# legatus_1_2.net
KiCad netlist of a schematic drawn in EAGLE
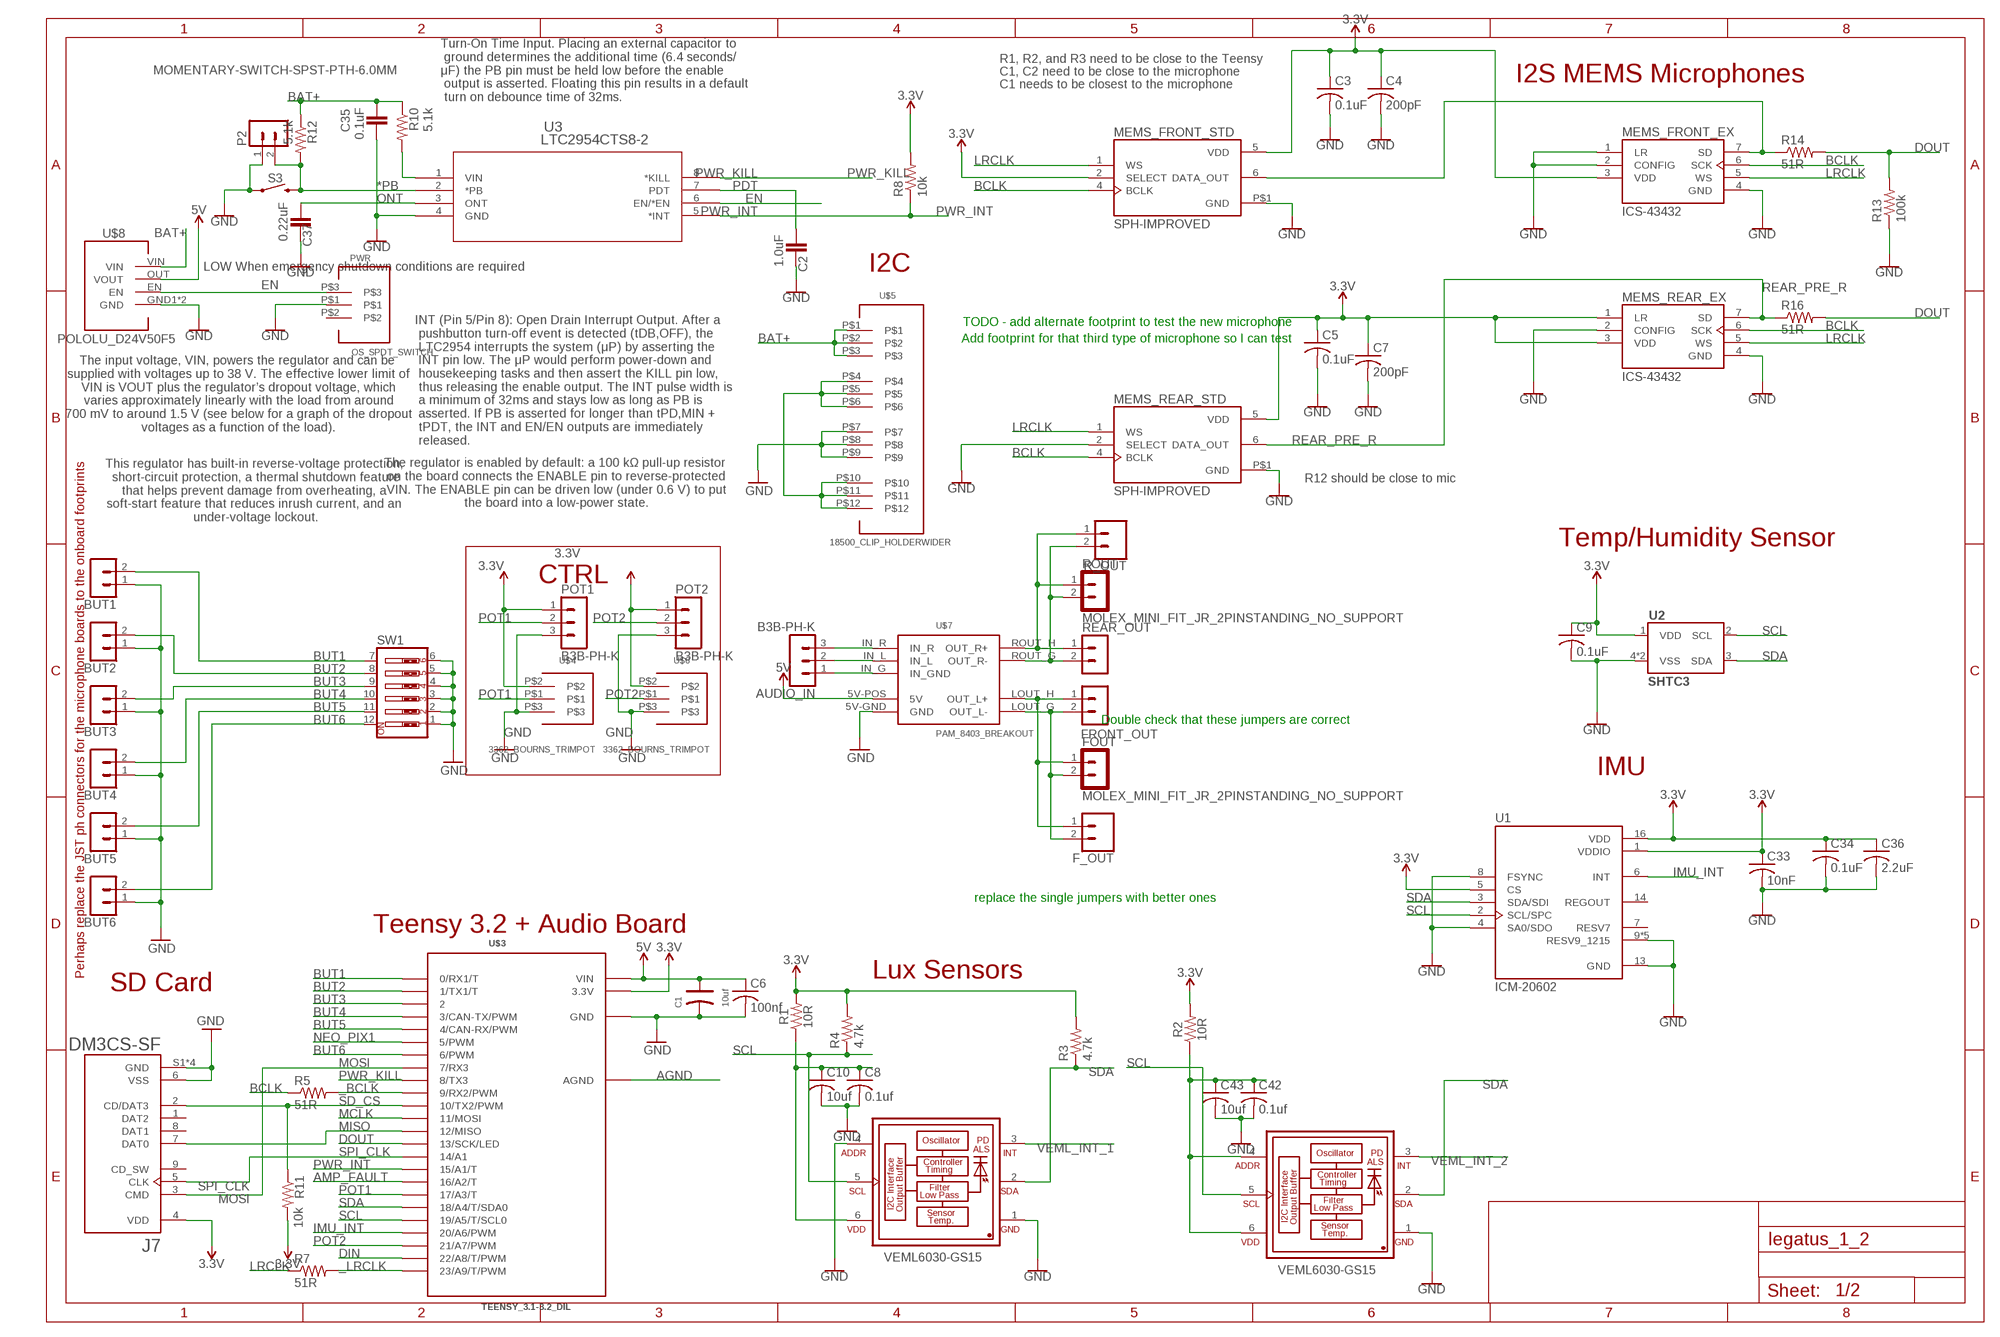
[diagram p0: schematic, sheet 1]
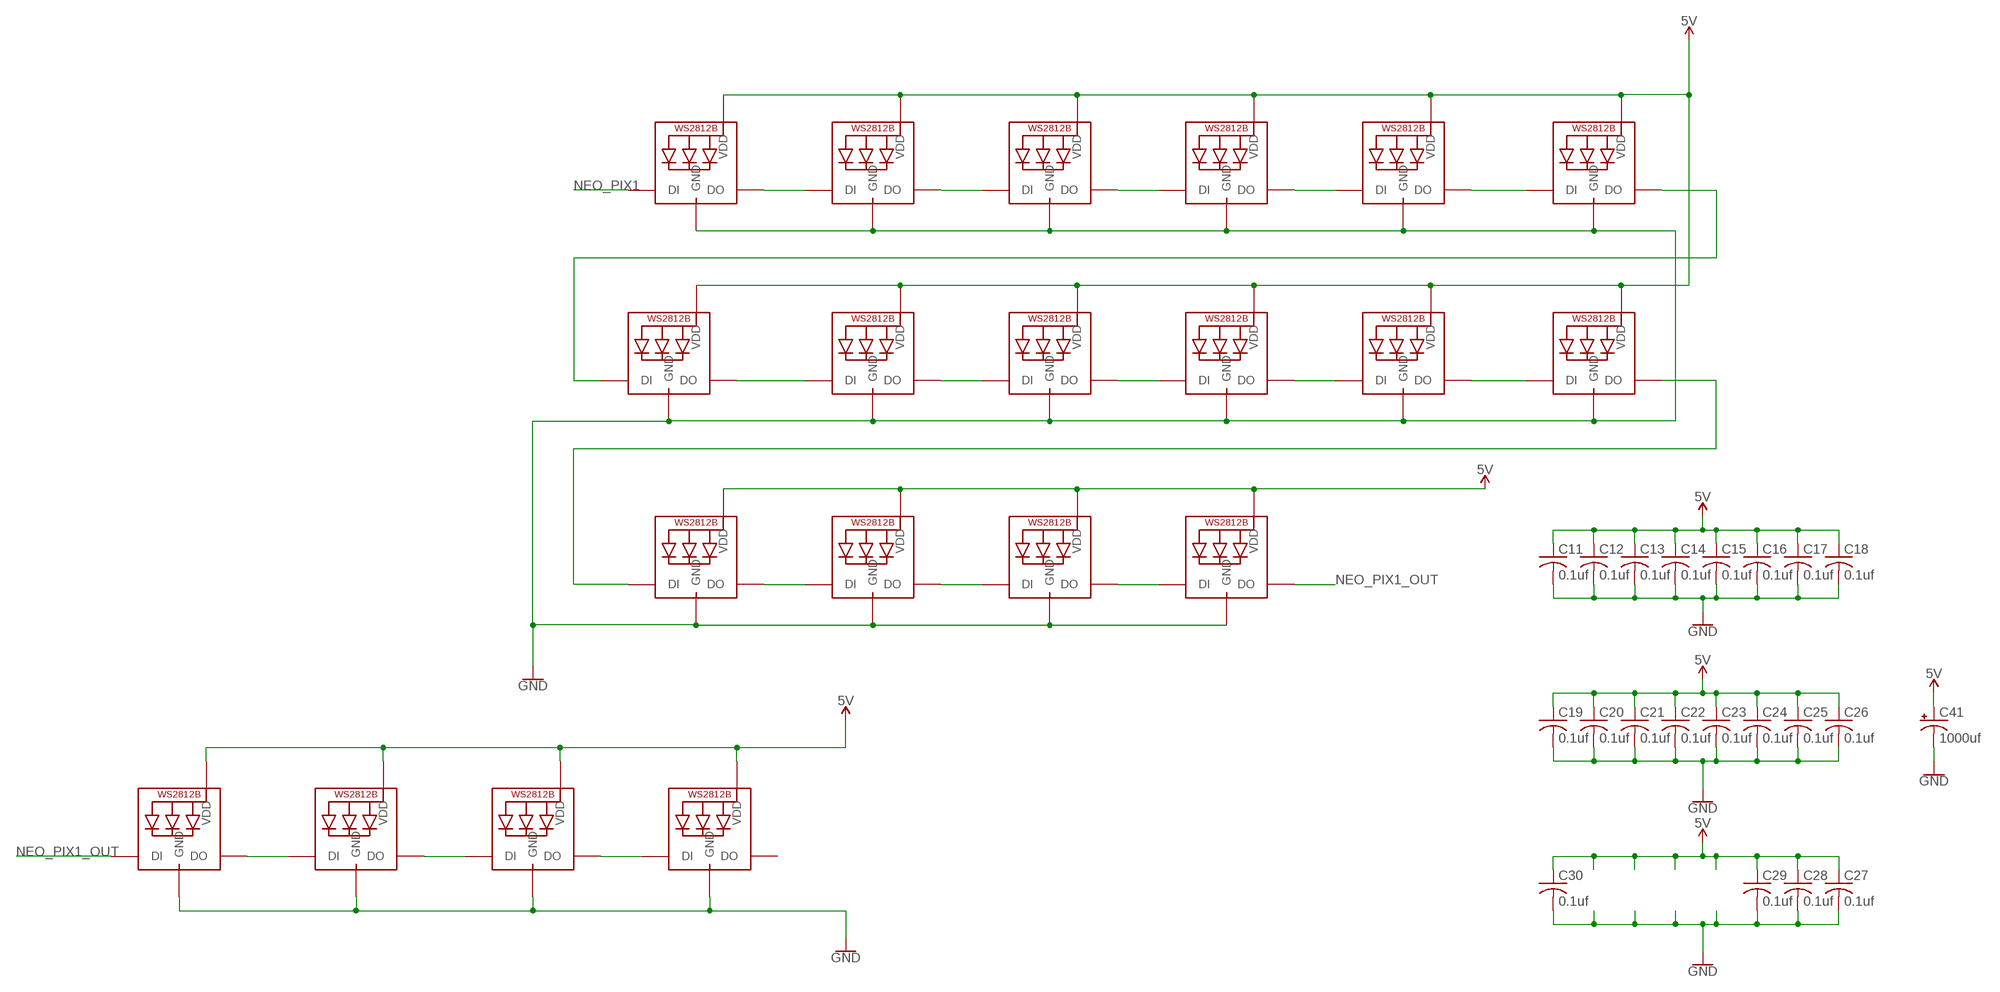
[diagram p1: schematic, sheet 2]

(export (version "E")
  (design (tool "Eeschema 10.0.6"))
  (components
    (comp (ref "C11")
      (value "0.1uf")
      (footprint "eagle-import:C0805")
      (libsource (lib "eagle-import") (part "rcl_334_C-USC0805"))
    )
    (comp (ref "C12")
      (value "0.1uf")
      (footprint "eagle-import:C0805")
      (libsource (lib "eagle-import") (part "rcl_334_C-USC0805"))
    )
    (comp (ref "C13")
      (value "0.1uf")
      (footprint "eagle-import:C0805")
      (libsource (lib "eagle-import") (part "rcl_334_C-USC0805"))
    )
    (comp (ref "C14")
      (value "0.1uf")
      (footprint "eagle-import:C0805")
      (libsource (lib "eagle-import") (part "rcl_334_C-USC0805"))
    )
    (comp (ref "C15")
      (value "0.1uf")
      (footprint "eagle-import:C0805")
      (libsource (lib "eagle-import") (part "rcl_334_C-USC0805"))
    )
    (comp (ref "C16")
      (value "0.1uf")
      (footprint "eagle-import:C0805")
      (libsource (lib "eagle-import") (part "rcl_334_C-USC0805"))
    )
    (comp (ref "C17")
      (value "0.1uf")
      (footprint "eagle-import:C0805")
      (libsource (lib "eagle-import") (part "rcl_334_C-USC0805"))
    )
    (comp (ref "C18")
      (value "0.1uf")
      (footprint "eagle-import:C0805")
      (libsource (lib "eagle-import") (part "rcl_334_C-USC0805"))
    )
    (comp (ref "C19")
      (value "0.1uf")
      (footprint "eagle-import:C0805")
      (libsource (lib "eagle-import") (part "rcl_334_C-USC0805"))
    )
    (comp (ref "C20")
      (value "0.1uf")
      (footprint "eagle-import:C0805")
      (libsource (lib "eagle-import") (part "rcl_334_C-USC0805"))
    )
    (comp (ref "C21")
      (value "0.1uf")
      (footprint "eagle-import:C0805")
      (libsource (lib "eagle-import") (part "rcl_334_C-USC0805"))
    )
    (comp (ref "C22")
      (value "0.1uf")
      (footprint "eagle-import:C0805")
      (libsource (lib "eagle-import") (part "rcl_334_C-USC0805"))
    )
    (comp (ref "C23")
      (value "0.1uf")
      (footprint "eagle-import:C0805")
      (libsource (lib "eagle-import") (part "rcl_334_C-USC0805"))
    )
    (comp (ref "C24")
      (value "0.1uf")
      (footprint "eagle-import:C0805")
      (libsource (lib "eagle-import") (part "rcl_334_C-USC0805"))
    )
    (comp (ref "C25")
      (value "0.1uf")
      (footprint "eagle-import:C0805")
      (libsource (lib "eagle-import") (part "rcl_334_C-USC0805"))
    )
    (comp (ref "C26")
      (value "0.1uf")
      (footprint "eagle-import:C0805")
      (libsource (lib "eagle-import") (part "rcl_334_C-USC0805"))
    )
    (comp (ref "C27")
      (value "0.1uf")
      (footprint "eagle-import:C0805")
      (libsource (lib "eagle-import") (part "rcl_334_C-USC0805"))
    )
    (comp (ref "C28")
      (value "0.1uf")
      (footprint "eagle-import:C0805")
      (libsource (lib "eagle-import") (part "rcl_334_C-USC0805"))
    )
    (comp (ref "C29")
      (value "0.1uf")
      (footprint "eagle-import:C0805")
      (libsource (lib "eagle-import") (part "rcl_334_C-USC0805"))
    )
    (comp (ref "C30")
      (value "0.1uf")
      (footprint "eagle-import:C0805")
      (libsource (lib "eagle-import") (part "rcl_334_C-USC0805"))
    )
    (comp (ref "C41")
      (value "1000uf")
      (footprint "eagle-import:153CLV-1010")
      (libsource (lib "eagle-import") (part "CPOL-US153CLV-1010"))
    )
    (comp (ref "LED1")
      (value "WS2812B_5050N")
      (footprint "eagle-import:WS2812B-NARROW")
      (libsource (lib "eagle-import") (part "WS2812B_5050N"))
    )
    (comp (ref "LED2")
      (value "WS2812B_5050N")
      (footprint "eagle-import:WS2812B-NARROW")
      (libsource (lib "eagle-import") (part "WS2812B_5050N"))
    )
    (comp (ref "LED3")
      (value "WS2812B_5050N")
      (footprint "eagle-import:WS2812B-NARROW")
      (libsource (lib "eagle-import") (part "WS2812B_5050N"))
    )
    (comp (ref "LED4")
      (value "WS2812B_5050N")
      (footprint "eagle-import:WS2812B-NARROW")
      (libsource (lib "eagle-import") (part "WS2812B_5050N"))
    )
    (comp (ref "LED5")
      (value "WS2812B_5050N")
      (footprint "eagle-import:WS2812B-NARROW")
      (libsource (lib "eagle-import") (part "WS2812B_5050N"))
    )
    (comp (ref "LED6")
      (value "WS2812B_5050N")
      (footprint "eagle-import:WS2812B-NARROW")
      (libsource (lib "eagle-import") (part "WS2812B_5050N"))
    )
    (comp (ref "LED7")
      (value "WS2812B_5050N")
      (footprint "eagle-import:WS2812B-NARROW")
      (libsource (lib "eagle-import") (part "WS2812B_5050N"))
    )
    (comp (ref "LED8")
      (value "WS2812B_5050N")
      (footprint "eagle-import:WS2812B-NARROW")
      (libsource (lib "eagle-import") (part "WS2812B_5050N"))
    )
    (comp (ref "LED9")
      (value "WS2812B_5050N")
      (footprint "eagle-import:WS2812B-NARROW")
      (libsource (lib "eagle-import") (part "WS2812B_5050N"))
    )
    (comp (ref "LED10")
      (value "WS2812B_5050N")
      (footprint "eagle-import:WS2812B-NARROW")
      (libsource (lib "eagle-import") (part "WS2812B_5050N"))
    )
    (comp (ref "LED11")
      (value "WS2812B_5050N")
      (footprint "eagle-import:WS2812B-NARROW")
      (libsource (lib "eagle-import") (part "WS2812B_5050N"))
    )
    (comp (ref "LED12")
      (value "WS2812B_5050N")
      (footprint "eagle-import:WS2812B-NARROW")
      (libsource (lib "eagle-import") (part "WS2812B_5050N"))
    )
    (comp (ref "LED13")
      (value "WS2812B_5050N")
      (footprint "eagle-import:WS2812B-NARROW")
      (libsource (lib "eagle-import") (part "WS2812B_5050N"))
    )
    (comp (ref "LED14")
      (value "WS2812B_5050N")
      (footprint "eagle-import:WS2812B-NARROW")
      (libsource (lib "eagle-import") (part "WS2812B_5050N"))
    )
    (comp (ref "LED15")
      (value "WS2812B_5050N")
      (footprint "eagle-import:WS2812B-NARROW")
      (libsource (lib "eagle-import") (part "WS2812B_5050N"))
    )
    (comp (ref "LED16")
      (value "WS2812B_5050N")
      (footprint "eagle-import:WS2812B-NARROW")
      (libsource (lib "eagle-import") (part "WS2812B_5050N"))
    )
    (comp (ref "LED17")
      (value "WS2812B_5050N")
      (footprint "eagle-import:WS2812B-NARROW")
      (libsource (lib "eagle-import") (part "WS2812B_5050N"))
    )
    (comp (ref "LED18")
      (value "WS2812B_5050N")
      (footprint "eagle-import:WS2812B-NARROW")
      (libsource (lib "eagle-import") (part "WS2812B_5050N"))
    )
    (comp (ref "LED19")
      (value "WS2812B_5050N")
      (footprint "eagle-import:WS2812B-NARROW")
      (libsource (lib "eagle-import") (part "WS2812B_5050N"))
    )
    (comp (ref "LED20")
      (value "WS2812B_5050N")
      (footprint "eagle-import:WS2812B-NARROW")
      (libsource (lib "eagle-import") (part "WS2812B_5050N"))
    )
    (comp (ref "AUDIO_IN")
      (value "B3B-PH-K")
      (footprint "eagle-import:B3B-PH-K")
      (libsource (lib "eagle-import") (part "B3B-PH-K"))
    )
    (comp (ref "BUT1")
      (value "B2B-PH-K")
      (footprint "eagle-import:B2B-PH-K")
      (libsource (lib "eagle-import") (part "B2B-PH-K"))
    )
    (comp (ref "BUT2")
      (value "B2B-PH-K")
      (footprint "eagle-import:B2B-PH-K")
      (libsource (lib "eagle-import") (part "B2B-PH-K"))
    )
    (comp (ref "BUT3")
      (value "B2B-PH-K")
      (footprint "eagle-import:B2B-PH-K")
      (libsource (lib "eagle-import") (part "B2B-PH-K"))
    )
    (comp (ref "BUT4")
      (value "B2B-PH-K")
      (footprint "eagle-import:B2B-PH-K")
      (libsource (lib "eagle-import") (part "B2B-PH-K"))
    )
    (comp (ref "BUT5")
      (value "B2B-PH-K")
      (footprint "eagle-import:B2B-PH-K")
      (libsource (lib "eagle-import") (part "B2B-PH-K"))
    )
    (comp (ref "BUT6")
      (value "B2B-PH-K")
      (footprint "eagle-import:B2B-PH-K")
      (libsource (lib "eagle-import") (part "B2B-PH-K"))
    )
    (comp (ref "C1")
      (value "10uf")
      (footprint "eagle-import:PC-D5.3MM")
      (fields (field (name "MPN") "KS 100uF/16V"))
      (libsource (lib "eagle-import") (part "DIP-ALUMINUM-47UF-16V(D5-H7MM)"))
    )
    (comp (ref "C2")
      (value "1.0uF")
      (footprint "eagle-import:CAPC2012X110")
      (libsource (lib "eagle-import") (part "CCHIP-0805(2012-METRIC)_"))
    )
    (comp (ref "C3")
      (value "0.1uF")
      (footprint "eagle-import:C0805")
      (libsource (lib "eagle-import") (part "rcl_334_C-USC0805"))
    )
    (comp (ref "C4")
      (value "200pF")
      (footprint "eagle-import:C0805")
      (libsource (lib "eagle-import") (part "rcl_334_C-USC0805"))
    )
    (comp (ref "C5")
      (value "0.1uF")
      (footprint "eagle-import:C0805")
      (libsource (lib "eagle-import") (part "rcl_334_C-USC0805"))
    )
    (comp (ref "C6")
      (value "100nf")
      (footprint "eagle-import:C2012")
      (libsource (lib "eagle-import") (part "C-USC2012"))
    )
    (comp (ref "C7")
      (value "200pF")
      (footprint "eagle-import:C0805")
      (libsource (lib "eagle-import") (part "rcl_334_C-USC0805"))
    )
    (comp (ref "C8")
      (value "0.1uf")
      (footprint "eagle-import:C0805")
      (libsource (lib "eagle-import") (part "rcl_334_C-USC0805"))
    )
    (comp (ref "C9")
      (value "0.1uF")
      (footprint "eagle-import:C0805")
      (libsource (lib "eagle-import") (part "rcl_334_C-USC0805"))
    )
    (comp (ref "C10")
      (value "10uf")
      (footprint "eagle-import:C0805")
      (libsource (lib "eagle-import") (part "rcl_334_C-USC0805"))
    )
    (comp (ref "C33")
      (value "10nF")
      (footprint "eagle-import:C0805")
      (libsource (lib "eagle-import") (part "rcl_334_C-USC0805"))
    )
    (comp (ref "C34")
      (value "0.1uF")
      (footprint "eagle-import:C0805")
      (libsource (lib "eagle-import") (part "rcl_334_C-USC0805"))
    )
    (comp (ref "C35")
      (value "0.1uF")
      (footprint "eagle-import:CAPC2012X110")
      (libsource (lib "eagle-import") (part "CCHIP-0805(2012-METRIC)_"))
    )
    (comp (ref "C36")
      (value "2.2uF")
      (footprint "eagle-import:C0805")
      (libsource (lib "eagle-import") (part "rcl_334_C-USC0805"))
    )
    (comp (ref "C37")
      (value "0.22uF")
      (footprint "eagle-import:CAPC2012X110")
      (libsource (lib "eagle-import") (part "CCHIP-0805(2012-METRIC)_"))
    )
    (comp (ref "C42")
      (value "0.1uf")
      (footprint "eagle-import:C0805")
      (libsource (lib "eagle-import") (part "rcl_334_C-USC0805"))
    )
    (comp (ref "C43")
      (value "10uf")
      (footprint "eagle-import:C0805")
      (libsource (lib "eagle-import") (part "rcl_334_C-USC0805"))
    )
    (comp (ref "FOUT")
      (value "MOLEX_MINI_FIT_JR_2PINSTANDING_NO_SUPPORT")
      (footprint "eagle-import:MOLEX_MINI_FIT_JR_2_PIN_STANDING_NO_SUPPORTS")
      (libsource (lib "eagle-import") (part "MOLEX_MINI_FIT_JR_2PINSTANDING_NO_SUPPORT"))
    )
    (comp (ref "FRONT_OUT")
      (value "B2B-PH-K")
      (footprint "eagle-import:B2B-PH-K")
      (libsource (lib "eagle-import") (part "B2B-PH-K"))
    )
    (comp (ref "F_OUT")
      (value "CONN_02")
      (footprint "eagle-import:1X02")
      (libsource (lib "eagle-import") (part "CONN_02"))
    )
    (comp (ref "J7")
      (value "DM3CS-SF")
      (footprint "eagle-import:HRS_DM3CS-SF")
      (fields (field (name "MF") "Hirose"))
      (libsource (lib "eagle-import") (part "DM3CS-SF"))
    )
    (comp (ref "MEMS_FRONT_EX")
      (value "ICS-43432")
      (footprint "eagle-import:ICS-43432")
      (fields
        (field (name "DIGIKEY_PARTNO") "1428-1053-2-ND")
        (field (name "MANUFACTURER") "TDK InvenSense")
        (field (name "CREATED_BY") "PCBLayout.com")
      )
      (libsource (lib "eagle-import") (part "ICS-43432"))
    )
    (comp (ref "MEMS_FRONT_STD")
      (value "SPH-IMPROVED")
      (footprint "eagle-import:MIC_SPH0645LM4H-B_LARGER_RING")
      (libsource (lib "eagle-import") (part "SPH-IMPROVED"))
    )
    (comp (ref "MEMS_REAR_EX")
      (value "ICS-43432")
      (footprint "eagle-import:ICS-43432")
      (fields
        (field (name "DIGIKEY_PARTNO") "1428-1053-2-ND")
        (field (name "MANUFACTURER") "TDK InvenSense")
        (field (name "CREATED_BY") "PCBLayout.com")
      )
      (libsource (lib "eagle-import") (part "ICS-43432"))
    )
    (comp (ref "MEMS_REAR_STD")
      (value "SPH-IMPROVED")
      (footprint "eagle-import:MIC_SPH0645LM4H-B_LARGER_RING")
      (libsource (lib "eagle-import") (part "SPH-IMPROVED"))
    )
    (comp (ref "P2")
      (value "B2B-PH-K")
      (footprint "eagle-import:B2B-PH-K")
      (libsource (lib "eagle-import") (part "B2B-PH-K"))
    )
    (comp (ref "POT1")
      (value "B3B-PH-K")
      (footprint "eagle-import:B3B-PH-K")
      (libsource (lib "eagle-import") (part "B3B-PH-K"))
    )
    (comp (ref "POT2")
      (value "B3B-PH-K")
      (footprint "eagle-import:B3B-PH-K")
      (libsource (lib "eagle-import") (part "B3B-PH-K"))
    )
    (comp (ref "PWR")
      (value "OS_SPDT_SWITCH")
      (footprint "eagle-import:OS_SPDT_SLIDE_SWITCH")
      (libsource (lib "eagle-import") (part "OS_SPDT_SWITCH"))
    )
    (comp (ref "R1")
      (value "10R")
      (footprint "eagle-import:R0805")
      (libsource (lib "eagle-import") (part "audio amplifier example_970892_R-US_R0805"))
    )
    (comp (ref "R2")
      (value "10R")
      (footprint "eagle-import:R0805")
      (libsource (lib "eagle-import") (part "audio amplifier example_970892_R-US_R0805"))
    )
    (comp (ref "R3")
      (value "4.7k")
      (footprint "eagle-import:M0805")
      (libsource (lib "eagle-import") (part "adafruit_420_R-US_M0805"))
    )
    (comp (ref "R4")
      (value "4.7k")
      (footprint "eagle-import:M0805")
      (libsource (lib "eagle-import") (part "adafruit_420_R-US_M0805"))
    )
    (comp (ref "R5")
      (value "51R")
      (footprint "eagle-import:M0805")
      (libsource (lib "eagle-import") (part "adafruit_420_R-US_M0805"))
    )
    (comp (ref "R7")
      (value "51R")
      (footprint "eagle-import:M0805")
      (libsource (lib "eagle-import") (part "adafruit_420_R-US_M0805"))
    )
    (comp (ref "R8")
      (value "10k")
      (footprint "eagle-import:R0805")
      (libsource (lib "eagle-import") (part "R-US_R0805"))
    )
    (comp (ref "R10")
      (value "5.1k")
      (footprint "eagle-import:R0805")
      (libsource (lib "eagle-import") (part "R-US_R0805"))
    )
    (comp (ref "R11")
      (value "10k")
      (footprint "eagle-import:M0805")
      (libsource (lib "eagle-import") (part "rcl_R-US_M0805"))
    )
    (comp (ref "R12")
      (value "5.1k")
      (footprint "eagle-import:R0805")
      (libsource (lib "eagle-import") (part "R-US_R0805"))
    )
    (comp (ref "R13")
      (value "100k")
      (footprint "eagle-import:M0805")
      (libsource (lib "eagle-import") (part "adafruit_420_R-US_M0805"))
    )
    (comp (ref "R14")
      (value "51R")
      (footprint "eagle-import:M0805")
      (libsource (lib "eagle-import") (part "adafruit_420_R-US_M0805"))
    )
    (comp (ref "R16")
      (value "51R")
      (footprint "eagle-import:M0805")
      (libsource (lib "eagle-import") (part "adafruit_420_R-US_M0805"))
    )
    (comp (ref "REAR_OUT")
      (value "B2B-PH-K")
      (footprint "eagle-import:B2B-PH-K")
      (libsource (lib "eagle-import") (part "B2B-PH-K"))
    )
    (comp (ref "ROUT")
      (value "MOLEX_MINI_FIT_JR_2PINSTANDING_NO_SUPPORT")
      (footprint "eagle-import:MOLEX_MINI_FIT_JR_2_PIN_STANDING_NO_SUPPORTS")
      (libsource (lib "eagle-import") (part "MOLEX_MINI_FIT_JR_2PINSTANDING_NO_SUPPORT"))
    )
    (comp (ref "R_OUT")
      (value "CONN_02")
      (footprint "eagle-import:1X02")
      (libsource (lib "eagle-import") (part "CONN_02"))
    )
    (comp (ref "S3")
      (value "MOMENTARY-SWITCH-SPST-PTH-6.0MM")
      (footprint "eagle-import:TACTILE_SWITCH_PTH_6.0MM")
      (libsource (lib "eagle-import") (part "MOMENTARY-SWITCH-SPST-PTH-6.0MM"))
    )
    (comp (ref "SW1")
      (value "SW_DIP-6")
      (footprint "eagle-import:EDG-06")
      (libsource (lib "eagle-import") (part "SW_DIP-6"))
    )
    (comp (ref "U$3")
      (value "TEENSY_3.1-3.2_DIL")
      (footprint "eagle-import:TEENSY_3.0-3.2&LC_DIL")
      (libsource (lib "eagle-import") (part "TEENSY_3.1-3.2_DIL"))
    )
    (comp (ref "U$4")
      (value "3362_BOURNS_TRIMPOT")
      (footprint "eagle-import:3362_BOURNS_TRIMPOT")
      (libsource (lib "eagle-import") (part "3362_BOURNS_TRIMPOT"))
    )
    (comp (ref "U$5")
      (value "18500_CLIP_HOLDERWIDER")
      (footprint "eagle-import:3PINBATTERY_CLIP_WIDER")
      (libsource (lib "eagle-import") (part "18500_CLIP_HOLDERWIDER"))
    )
    (comp (ref "U$6")
      (value "3362_BOURNS_TRIMPOT")
      (footprint "eagle-import:3362_BOURNS_TRIMPOT")
      (libsource (lib "eagle-import") (part "3362_BOURNS_TRIMPOT"))
    )
    (comp (ref "U$7")
      (value "PAM_8403_BREAKOUT")
      (footprint "eagle-import:PAM8403_BREAKOUT")
      (libsource (lib "eagle-import") (part "PAM_8403_BREAKOUT"))
    )
    (comp (ref "U$8")
      (value "POLOLU_D24V50F5")
      (footprint "eagle-import:POLOLU_D24V50F5")
      (libsource (lib "eagle-import") (part "POLOLU_D24V50F5"))
    )
    (comp (ref "U1")
      (value "ICM-20602")
      (footprint "eagle-import:PQFN50P300X300X80-16N")
      (fields (field (name "MF") "TDK InvenSense"))
      (libsource (lib "eagle-import") (part "ICM-20602"))
    )
    (comp (ref "U2")
      (value "SHTC3")
      (footprint "eagle-import:SHTC3")
      (libsource (lib "eagle-import") (part "SHTC3"))
    )
    (comp (ref "U3")
      (value "LTC2954CTS8-2")
      (footprint "eagle-import:TSOT-23_TS8")
      (fields (field (name "MF") "Analog Devices / Linear Technology"))
      (libsource (lib "eagle-import") (part "LTC2954CTS8-2"))
    )
    (comp (ref "VMEL_FRONT")
      (value "VEML6030-GS15")
      (footprint "eagle-import:VISHAY_VEML6030_2X2X0.87")
      (fields (field (name "MF") "Vishay Semiconductor"))
      (libsource (lib "eagle-import") (part "VEML6030-GS15"))
    )
    (comp (ref "VMEL_REAR")
      (value "VEML6030-GS15")
      (footprint "eagle-import:VISHAY_VEML6030_2X2X0.87")
      (fields (field (name "MF") "Vishay Semiconductor"))
      (libsource (lib "eagle-import") (part "VEML6030-GS15"))
    )
  )
  (nets
    (net (code "1") (name "*PB") (class "Default")
      (node (ref "P2") (pin "2") (pinfunction "2_2") (pintype "passive"))
      (node (ref "R12") (pin "2") (pinfunction "2_2") (pintype "passive"))
      (node (ref "S3") (pin "3") (pinfunction "2_3") (pintype "passive"))
      (node (ref "U3") (pin "2") (pinfunction "*PB_2") (pintype "input"))
    )
    (net (code "2") (name "3.3V") (class "Default")
      (node (ref "C3") (pin "1") (pinfunction "1_1") (pintype "passive"))
      (node (ref "C33") (pin "1") (pinfunction "1_1") (pintype "passive"))
      (node (ref "C34") (pin "1") (pinfunction "1_1") (pintype "passive"))
      (node (ref "C36") (pin "1") (pinfunction "1_1") (pintype "passive"))
      (node (ref "C4") (pin "1") (pinfunction "1_1") (pintype "passive"))
      (node (ref "C5") (pin "1") (pinfunction "1_1") (pintype "passive"))
      (node (ref "C7") (pin "1") (pinfunction "1_1") (pintype "passive"))
      (node (ref "C9") (pin "1") (pinfunction "1_1") (pintype "passive"))
      (node (ref "J7") (pin "4") (pinfunction "VDD_4") (pintype "passive"))
      (node (ref "MEMS_FRONT_EX") (pin "3") (pinfunction "VDD_3") (pintype "power_in"))
      (node (ref "MEMS_FRONT_STD") (pin "2") (pinfunction "SELECT_2") (pintype "input"))
      (node (ref "MEMS_FRONT_STD") (pin "5") (pinfunction "VDD_5") (pintype "power_in"))
      (node (ref "MEMS_REAR_EX") (pin "1") (pinfunction "LR_1") (pintype "input"))
      (node (ref "MEMS_REAR_EX") (pin "3") (pinfunction "VDD_3") (pintype "power_in"))
      (node (ref "MEMS_REAR_STD") (pin "5") (pinfunction "VDD_5") (pintype "power_in"))
      (node (ref "POT1") (pin "1") (pinfunction "1_1") (pintype "passive"))
      (node (ref "POT2") (pin "1") (pinfunction "1_1") (pintype "passive"))
      (node (ref "R1") (pin "2") (pinfunction "2_2") (pintype "passive"))
      (node (ref "R11") (pin "2") (pinfunction "2_2") (pintype "passive"))
      (node (ref "R2") (pin "2") (pinfunction "2_2") (pintype "passive"))
      (node (ref "R3") (pin "2") (pinfunction "2_2") (pintype "passive"))
      (node (ref "R4") (pin "2") (pinfunction "2_2") (pintype "passive"))
      (node (ref "R8") (pin "2") (pinfunction "2_2") (pintype "passive"))
      (node (ref "U$3") (pin "3.3V") (pinfunction "3.3V_3.3V") (pintype "power_in"))
      (node (ref "U$4") (pin "P$2") (pinfunction "P$2_P$2") (pintype "bidirectional"))
      (node (ref "U$6") (pin "P$2") (pinfunction "P$2_P$2") (pintype "bidirectional"))
      (node (ref "U1") (pin "1") (pinfunction "VDDIO_1") (pintype "power_in"))
      (node (ref "U1") (pin "16") (pinfunction "VDD_16") (pintype "power_in"))
      (node (ref "U1") (pin "5") (pinfunction "CS_5") (pintype "input"))
      (node (ref "U2") (pin "1") (pinfunction "VDD_1") (pintype "bidirectional"))
    )
    (net (code "3") (name "5V") (class "Default")
      (node (ref "C1") (pin "+") (pinfunction "+_+") (pintype "passive"))
      (node (ref "C11") (pin "1") (pinfunction "1_1") (pintype "passive"))
      (node (ref "C12") (pin "1") (pinfunction "1_1") (pintype "passive"))
      (node (ref "C13") (pin "1") (pinfunction "1_1") (pintype "passive"))
      (node (ref "C14") (pin "1") (pinfunction "1_1") (pintype "passive"))
      (node (ref "C15") (pin "1") (pinfunction "1_1") (pintype "passive"))
      (node (ref "C16") (pin "1") (pinfunction "1_1") (pintype "passive"))
      (node (ref "C17") (pin "1") (pinfunction "1_1") (pintype "passive"))
      (node (ref "C18") (pin "1") (pinfunction "1_1") (pintype "passive"))
      (node (ref "C19") (pin "1") (pinfunction "1_1") (pintype "passive"))
      (node (ref "C20") (pin "1") (pinfunction "1_1") (pintype "passive"))
      (node (ref "C21") (pin "1") (pinfunction "1_1") (pintype "passive"))
      (node (ref "C22") (pin "1") (pinfunction "1_1") (pintype "passive"))
      (node (ref "C23") (pin "1") (pinfunction "1_1") (pintype "passive"))
      (node (ref "C24") (pin "1") (pinfunction "1_1") (pintype "passive"))
      (node (ref "C25") (pin "1") (pinfunction "1_1") (pintype "passive"))
      (node (ref "C26") (pin "1") (pinfunction "1_1") (pintype "passive"))
      (node (ref "C27") (pin "1") (pinfunction "1_1") (pintype "passive"))
      (node (ref "C28") (pin "1") (pinfunction "1_1") (pintype "passive"))
      (node (ref "C29") (pin "1") (pinfunction "1_1") (pintype "passive"))
      (node (ref "C30") (pin "1") (pinfunction "1_1") (pintype "passive"))
      (node (ref "C41") (pin "+") (pinfunction "+_+") (pintype "passive"))
      (node (ref "C6") (pin "1") (pinfunction "1_1") (pintype "passive"))
      (node (ref "LED1") (pin "1-VDD") (pinfunction "VDD_1-VDD") (pintype "power_in"))
      (node (ref "LED10") (pin "1-VDD") (pinfunction "VDD_1-VDD") (pintype "power_in"))
      (node (ref "LED11") (pin "1-VDD") (pinfunction "VDD_1-VDD") (pintype "power_in"))
      (node (ref "LED12") (pin "1-VDD") (pinfunction "VDD_1-VDD") (pintype "power_in"))
      (node (ref "LED13") (pin "1-VDD") (pinfunction "VDD_1-VDD") (pintype "power_in"))
      (node (ref "LED14") (pin "1-VDD") (pinfunction "VDD_1-VDD") (pintype "power_in"))
      (node (ref "LED15") (pin "1-VDD") (pinfunction "VDD_1-VDD") (pintype "power_in"))
      (node (ref "LED16") (pin "1-VDD") (pinfunction "VDD_1-VDD") (pintype "power_in"))
      (node (ref "LED17") (pin "1-VDD") (pinfunction "VDD_1-VDD") (pintype "power_in"))
      (node (ref "LED18") (pin "1-VDD") (pinfunction "VDD_1-VDD") (pintype "power_in"))
      (node (ref "LED19") (pin "1-VDD") (pinfunction "VDD_1-VDD") (pintype "power_in"))
      (node (ref "LED2") (pin "1-VDD") (pinfunction "VDD_1-VDD") (pintype "power_in"))
      (node (ref "LED20") (pin "1-VDD") (pinfunction "VDD_1-VDD") (pintype "power_in"))
      (node (ref "LED3") (pin "1-VDD") (pinfunction "VDD_1-VDD") (pintype "power_in"))
      (node (ref "LED4") (pin "1-VDD") (pinfunction "VDD_1-VDD") (pintype "power_in"))
      (node (ref "LED5") (pin "1-VDD") (pinfunction "VDD_1-VDD") (pintype "power_in"))
      (node (ref "LED6") (pin "1-VDD") (pinfunction "VDD_1-VDD") (pintype "power_in"))
      (node (ref "LED7") (pin "1-VDD") (pinfunction "VDD_1-VDD") (pintype "power_in"))
      (node (ref "LED8") (pin "1-VDD") (pinfunction "VDD_1-VDD") (pintype "power_in"))
      (node (ref "LED9") (pin "1-VDD") (pinfunction "VDD_1-VDD") (pintype "power_in"))
      (node (ref "U$3") (pin "VIN") (pinfunction "VIN_VIN") (pintype "power_in"))
      (node (ref "U$7") (pin "5V-POS") (pinfunction "5V_5V-POS") (pintype "bidirectional"))
      (node (ref "U$8") (pin "OUT") (pinfunction "VOUT_OUT") (pintype "bidirectional"))
    )
    (net (code "4") (name "AGND") (class "Default")
      (node (ref "U$3") (pin "AGND") (pinfunction "AGND_AGND") (pintype "power_in"))
    )
    (net (code "5") (name "AMP_FAULT") (class "Default")
      (node (ref "U$3") (pin "16/A2") (pinfunction "16/A2/T_16/A2") (pintype "bidirectional"))
    )
    (net (code "6") (name "BAT+") (class "Default")
      (node (ref "C35") (pin "1") (pinfunction "1_1") (pintype "passive"))
      (node (ref "R10") (pin "1") (pinfunction "1_1") (pintype "passive"))
      (node (ref "R12") (pin "1") (pinfunction "1_1") (pintype "passive"))
      (node (ref "U$5") (pin "P$1") (pinfunction "P$1_P$1") (pintype "bidirectional"))
      (node (ref "U$5") (pin "P$2") (pinfunction "P$2_P$2") (pintype "bidirectional"))
      (node (ref "U$5") (pin "P$3") (pinfunction "P$3_P$3") (pintype "bidirectional"))
      (node (ref "U$8") (pin "VIN") (pinfunction "VIN_VIN") (pintype "bidirectional"))
    )
    (net (code "7") (name "BCLK") (class "Default")
      (node (ref "MEMS_FRONT_EX") (pin "6") (pinfunction "SCK_6") (pintype "input"))
      (node (ref "MEMS_FRONT_STD") (pin "4") (pinfunction "BCLK_4") (pintype "input"))
      (node (ref "MEMS_REAR_EX") (pin "6") (pinfunction "SCK_6") (pintype "input"))
      (node (ref "MEMS_REAR_STD") (pin "4") (pinfunction "BCLK_4") (pintype "input"))
      (node (ref "R5") (pin "1") (pinfunction "1_1") (pintype "passive"))
    )
    (net (code "8") (name "BUT1") (class "Default")
      (node (ref "BUT1") (pin "2") (pinfunction "2_2") (pintype "passive"))
      (node (ref "SW1") (pin "7") (pinfunction "7_7") (pintype "passive"))
      (node (ref "U$3") (pin "0") (pinfunction "0/RX1/T_0") (pintype "bidirectional"))
    )
    (net (code "9") (name "BUT2") (class "Default")
      (node (ref "BUT2") (pin "2") (pinfunction "2_2") (pintype "passive"))
      (node (ref "SW1") (pin "8") (pinfunction "8_8") (pintype "passive"))
      (node (ref "U$3") (pin "1") (pinfunction "1/TX1/T_1") (pintype "bidirectional"))
    )
    (net (code "10") (name "BUT3") (class "Default")
      (node (ref "BUT3") (pin "2") (pinfunction "2_2") (pintype "passive"))
      (node (ref "SW1") (pin "9") (pinfunction "9_9") (pintype "passive"))
      (node (ref "U$3") (pin "2") (pinfunction "2_2") (pintype "bidirectional"))
    )
    (net (code "11") (name "BUT4") (class "Default")
      (node (ref "BUT4") (pin "2") (pinfunction "2_2") (pintype "passive"))
      (node (ref "SW1") (pin "10") (pinfunction "10_10") (pintype "passive"))
      (node (ref "U$3") (pin "3") (pinfunction "3/CAN-TX/PWM_3") (pintype "bidirectional"))
    )
    (net (code "12") (name "BUT5") (class "Default")
      (node (ref "BUT5") (pin "2") (pinfunction "2_2") (pintype "passive"))
      (node (ref "SW1") (pin "11") (pinfunction "11_11") (pintype "passive"))
      (node (ref "U$3") (pin "4") (pinfunction "4/CAN-RX/PWM_4") (pintype "bidirectional"))
    )
    (net (code "13") (name "BUT6") (class "Default")
      (node (ref "BUT6") (pin "2") (pinfunction "2_2") (pintype "passive"))
      (node (ref "SW1") (pin "12") (pinfunction "12_12") (pintype "passive"))
      (node (ref "U$3") (pin "6") (pinfunction "6/PWM_6") (pintype "bidirectional"))
    )
    (net (code "14") (name "DIN") (class "Default")
      (node (ref "U$3") (pin "22/A8") (pinfunction "22/A8/T/PWM_22/A8") (pintype "bidirectional"))
    )
    (net (code "15") (name "DOUT") (class "Default")
      (node (ref "R13") (pin "2") (pinfunction "2_2") (pintype "passive"))
      (node (ref "R14") (pin "2") (pinfunction "2_2") (pintype "passive"))
      (node (ref "R16") (pin "2") (pinfunction "2_2") (pintype "passive"))
      (node (ref "U$3") (pin "13") (pinfunction "13/SCK/LED_13") (pintype "bidirectional"))
    )
    (net (code "16") (name "EN") (class "Default")
      (node (ref "PWR") (pin "P$3") (pinfunction "P$3_P$3") (pintype "bidirectional"))
      (node (ref "U$8") (pin "EN") (pinfunction "EN_EN") (pintype "bidirectional"))
      (node (ref "U3") (pin "6") (pinfunction "EN/*EN_6") (pintype "output"))
    )
    (net (code "17") (name "GND") (class "Default")
      (node (ref "BUT1") (pin "1") (pinfunction "1_1") (pintype "passive"))
      (node (ref "BUT2") (pin "1") (pinfunction "1_1") (pintype "passive"))
      (node (ref "BUT3") (pin "1") (pinfunction "1_1") (pintype "passive"))
      (node (ref "BUT4") (pin "1") (pinfunction "1_1") (pintype "passive"))
      (node (ref "BUT5") (pin "1") (pinfunction "1_1") (pintype "passive"))
      (node (ref "BUT6") (pin "1") (pinfunction "1_1") (pintype "passive"))
      (node (ref "C1") (pin "-") (pinfunction "-_-") (pintype "passive"))
      (node (ref "C10") (pin "2") (pinfunction "2_2") (pintype "passive"))
      (node (ref "C11") (pin "2") (pinfunction "2_2") (pintype "passive"))
      (node (ref "C12") (pin "2") (pinfunction "2_2") (pintype "passive"))
      (node (ref "C13") (pin "2") (pinfunction "2_2") (pintype "passive"))
      (node (ref "C14") (pin "2") (pinfunction "2_2") (pintype "passive"))
      (node (ref "C15") (pin "2") (pinfunction "2_2") (pintype "passive"))
      (node (ref "C16") (pin "2") (pinfunction "2_2") (pintype "passive"))
      (node (ref "C17") (pin "2") (pinfunction "2_2") (pintype "passive"))
      (node (ref "C18") (pin "2") (pinfunction "2_2") (pintype "passive"))
      (node (ref "C19") (pin "2") (pinfunction "2_2") (pintype "passive"))
      (node (ref "C2") (pin "2") (pinfunction "2_2") (pintype "passive"))
      (node (ref "C20") (pin "2") (pinfunction "2_2") (pintype "passive"))
      (node (ref "C21") (pin "2") (pinfunction "2_2") (pintype "passive"))
      (node (ref "C22") (pin "2") (pinfunction "2_2") (pintype "passive"))
      (node (ref "C23") (pin "2") (pinfunction "2_2") (pintype "passive"))
      (node (ref "C24") (pin "2") (pinfunction "2_2") (pintype "passive"))
      (node (ref "C25") (pin "2") (pinfunction "2_2") (pintype "passive"))
      (node (ref "C26") (pin "2") (pinfunction "2_2") (pintype "passive"))
      (node (ref "C27") (pin "2") (pinfunction "2_2") (pintype "passive"))
      (node (ref "C28") (pin "2") (pinfunction "2_2") (pintype "passive"))
      (node (ref "C29") (pin "2") (pinfunction "2_2") (pintype "passive"))
      (node (ref "C3") (pin "2") (pinfunction "2_2") (pintype "passive"))
      (node (ref "C30") (pin "2") (pinfunction "2_2") (pintype "passive"))
      (node (ref "C33") (pin "2") (pinfunction "2_2") (pintype "passive"))
      (node (ref "C34") (pin "2") (pinfunction "2_2") (pintype "passive"))
      (node (ref "C35") (pin "2") (pinfunction "2_2") (pintype "passive"))
      (node (ref "C36") (pin "2") (pinfunction "2_2") (pintype "passive"))
      (node (ref "C37") (pin "2") (pinfunction "2_2") (pintype "passive"))
      (node (ref "C4") (pin "2") (pinfunction "2_2") (pintype "passive"))
      (node (ref "C41") (pin "-") (pinfunction "-_-") (pintype "passive"))
      (node (ref "C42") (pin "2") (pinfunction "2_2") (pintype "passive"))
      (node (ref "C43") (pin "2") (pinfunction "2_2") (pintype "passive"))
      (node (ref "C5") (pin "2") (pinfunction "2_2") (pintype "passive"))
      (node (ref "C6") (pin "2") (pinfunction "2_2") (pintype "passive"))
      (node (ref "C7") (pin "2") (pinfunction "2_2") (pintype "passive"))
      (node (ref "C8") (pin "2") (pinfunction "2_2") (pintype "passive"))
      (node (ref "C9") (pin "2") (pinfunction "2_2") (pintype "passive"))
      (node (ref "J7") (pin "6") (pinfunction "VSS_6") (pintype "passive"))
      (node (ref "J7") (pin "S1") (pinfunction "GND_S1") (pintype "passive"))
      (node (ref "J7") (pin "S2") (pinfunction "GND_S2") (pintype "passive"))
      (node (ref "J7") (pin "S3") (pinfunction "GND_S3") (pintype "passive"))
      (node (ref "J7") (pin "S5") (pinfunction "GND_S5") (pintype "passive"))
      (node (ref "LED1") (pin "3-GND") (pinfunction "GND_3-GND") (pintype "power_in"))
      (node (ref "LED10") (pin "3-GND") (pinfunction "GND_3-GND") (pintype "power_in"))
      (node (ref "LED11") (pin "3-GND") (pinfunction "GND_3-GND") (pintype "power_in"))
      (node (ref "LED12") (pin "3-GND") (pinfunction "GND_3-GND") (pintype "power_in"))
      (node (ref "LED13") (pin "3-GND") (pinfunction "GND_3-GND") (pintype "power_in"))
      (node (ref "LED14") (pin "3-GND") (pinfunction "GND_3-GND") (pintype "power_in"))
      (node (ref "LED15") (pin "3-GND") (pinfunction "GND_3-GND") (pintype "power_in"))
      (node (ref "LED16") (pin "3-GND") (pinfunction "GND_3-GND") (pintype "power_in"))
      (node (ref "LED17") (pin "3-GND") (pinfunction "GND_3-GND") (pintype "power_in"))
      (node (ref "LED18") (pin "3-GND") (pinfunction "GND_3-GND") (pintype "power_in"))
      (node (ref "LED19") (pin "3-GND") (pinfunction "GND_3-GND") (pintype "power_in"))
      (node (ref "LED2") (pin "3-GND") (pinfunction "GND_3-GND") (pintype "power_in"))
      (node (ref "LED20") (pin "3-GND") (pinfunction "GND_3-GND") (pintype "power_in"))
      (node (ref "LED3") (pin "3-GND") (pinfunction "GND_3-GND") (pintype "power_in"))
      (node (ref "LED4") (pin "3-GND") (pinfunction "GND_3-GND") (pintype "power_in"))
      (node (ref "LED5") (pin "3-GND") (pinfunction "GND_3-GND") (pintype "power_in"))
      (node (ref "LED6") (pin "3-GND") (pinfunction "GND_3-GND") (pintype "power_in"))
      (node (ref "LED7") (pin "3-GND") (pinfunction "GND_3-GND") (pintype "power_in"))
      (node (ref "LED8") (pin "3-GND") (pinfunction "GND_3-GND") (pintype "power_in"))
      (node (ref "LED9") (pin "3-GND") (pinfunction "GND_3-GND") (pintype "power_in"))
      (node (ref "MEMS_FRONT_EX") (pin "1") (pinfunction "LR_1") (pintype "input"))
      (node (ref "MEMS_FRONT_EX") (pin "2") (pinfunction "CONFIG_2") (pintype "input"))
      (node (ref "MEMS_FRONT_EX") (pin "4") (pinfunction "GND_4") (pintype "power_in"))
      (node (ref "MEMS_FRONT_STD") (pin "P$1") (pinfunction "GND_P$1") (pintype "power_in"))
      (node (ref "MEMS_REAR_EX") (pin "2") (pinfunction "CONFIG_2") (pintype "input"))
      (node (ref "MEMS_REAR_EX") (pin "4") (pinfunction "GND_4") (pintype "power_in"))
      (node (ref "MEMS_REAR_STD") (pin "2") (pinfunction "SELECT_2") (pintype "input"))
      (node (ref "MEMS_REAR_STD") (pin "P$1") (pinfunction "GND_P$1") (pintype "power_in"))
      (node (ref "P2") (pin "1") (pinfunction "1_1") (pintype "passive"))
      (node (ref "POT1") (pin "3") (pinfunction "3_3") (pintype "passive"))
      (node (ref "POT2") (pin "3") (pinfunction "3_3") (pintype "passive"))
      (node (ref "PWR") (pin "P$1") (pinfunction "P$1_P$1") (pintype "bidirectional"))
      (node (ref "R13") (pin "1") (pinfunction "1_1") (pintype "passive"))
      (node (ref "S3") (pin "1") (pinfunction "1_1") (pintype "passive"))
      (node (ref "SW1") (pin "1") (pinfunction "1_1") (pintype "passive"))
      (node (ref "SW1") (pin "2") (pinfunction "2_2") (pintype "passive"))
      (node (ref "SW1") (pin "3") (pinfunction "3_3") (pintype "passive"))
      (node (ref "SW1") (pin "4") (pinfunction "4_4") (pintype "passive"))
      (node (ref "SW1") (pin "5") (pinfunction "5_5") (pintype "passive"))
      (node (ref "SW1") (pin "6") (pinfunction "6_6") (pintype "passive"))
      (node (ref "U$3") (pin "GND") (pinfunction "GND_GND") (pintype "power_in"))
      (node (ref "U$4") (pin "P$3") (pinfunction "P$3_P$3") (pintype "bidirectional"))
      (node (ref "U$5") (pin "P$7") (pinfunction "P$7_P$7") (pintype "bidirectional"))
      (node (ref "U$5") (pin "P$8") (pinfunction "P$8_P$8") (pintype "bidirectional"))
      (node (ref "U$5") (pin "P$9") (pinfunction "P$9_P$9") (pintype "bidirectional"))
      (node (ref "U$6") (pin "P$3") (pinfunction "P$3_P$3") (pintype "bidirectional"))
      (node (ref "U$7") (pin "5V-GND") (pinfunction "GND_5V-GND") (pintype "bidirectional"))
      (node (ref "U$8") (pin "GND1") (pinfunction "GND_GND1") (pintype "bidirectional"))
      (node (ref "U$8") (pin "GND2") (pinfunction "GND_GND2") (pintype "bidirectional"))
      (node (ref "U1") (pin "10") (pinfunction "RESV9_1215_10") (pintype "passive"))
      (node (ref "U1") (pin "11") (pinfunction "RESV9_1215_11") (pintype "passive"))
      (node (ref "U1") (pin "12") (pinfunction "RESV9_1215_12") (pintype "passive"))
      (node (ref "U1") (pin "13") (pinfunction "GND_13") (pintype "power_in"))
      (node (ref "U1") (pin "15") (pinfunction "RESV9_1215_15") (pintype "passive"))
      (node (ref "U1") (pin "4") (pinfunction "SA0/SDO_4") (pintype "output"))
      (node (ref "U1") (pin "8") (pinfunction "FSYNC_8") (pintype "input"))
      (node (ref "U1") (pin "9") (pinfunction "RESV9_1215_9") (pintype "passive"))
      (node (ref "U2") (pin "4") (pinfunction "VSS_4") (pintype "bidirectional"))
      (node (ref "U2") (pin "5") (pinfunction "VSS_5") (pintype "bidirectional"))
      (node (ref "U3") (pin "4") (pinfunction "GND_4") (pintype "power_in"))
      (node (ref "VMEL_FRONT") (pin "1") (pinfunction "GND_1") (pintype "power_in"))
      (node (ref "VMEL_FRONT") (pin "4") (pinfunction "ADDR_4") (pintype "bidirectional"))
      (node (ref "VMEL_REAR") (pin "1") (pinfunction "GND_1") (pintype "power_in"))
    )
    (net (code "18") (name "IMU_INT") (class "Default")
      (node (ref "U$3") (pin "20/A6") (pinfunction "20/A6/PWM_20/A6") (pintype "bidirectional"))
      (node (ref "U1") (pin "6") (pinfunction "INT_6") (pintype "output"))
    )
    (net (code "19") (name "LRCLK") (class "Default")
      (node (ref "MEMS_FRONT_EX") (pin "5") (pinfunction "WS_5") (pintype "input"))
      (node (ref "MEMS_FRONT_STD") (pin "1") (pinfunction "WS_1") (pintype "input"))
      (node (ref "MEMS_REAR_EX") (pin "5") (pinfunction "WS_5") (pintype "input"))
      (node (ref "MEMS_REAR_STD") (pin "1") (pinfunction "WS_1") (pintype "input"))
      (node (ref "R7") (pin "1") (pinfunction "1_1") (pintype "passive"))
    )
    (net (code "20") (name "MCLK") (class "Default")
      (node (ref "U$3") (pin "11") (pinfunction "11/MOSI_11") (pintype "bidirectional"))
    )
    (net (code "21") (name "MISO") (class "Default")
      (node (ref "J7") (pin "7") (pinfunction "DAT0_7") (pintype "passive"))
      (node (ref "U$3") (pin "12") (pinfunction "12/MISO_12") (pintype "bidirectional"))
    )
    (net (code "22") (name "MOSI") (class "Default")
      (node (ref "J7") (pin "3") (pinfunction "CMD_3") (pintype "passive"))
      (node (ref "U$3") (pin "7") (pinfunction "7/RX3_7") (pintype "bidirectional"))
    )
    (net (code "23") (name "NEO_PIX1") (class "Default")
      (node (ref "LED1") (pin "4-DIN") (pinfunction "DI_4-DIN") (pintype "input"))
      (node (ref "U$3") (pin "5") (pinfunction "5/PWM_5") (pintype "bidirectional"))
    )
    (net (code "24") (name "NEO_PIX1_OUT") (class "Default")
      (node (ref "LED16") (pin "2-DOUT") (pinfunction "DO_2-DOUT") (pintype "output"))
      (node (ref "LED17") (pin "4-DIN") (pinfunction "DI_4-DIN") (pintype "input"))
    )
    (net (code "25") (name "Net-(AUDIO_IN-Pad2)") (class "Default")
      (node (ref "AUDIO_IN") (pin "2") (pinfunction "2_2") (pintype "passive"))
      (node (ref "U$7") (pin "IN_L") (pinfunction "IN_L_IN_L") (pintype "bidirectional"))
    )
    (net (code "26") (name "Net-(AUDIO_IN-Pad3)") (class "Default")
      (node (ref "AUDIO_IN") (pin "3") (pinfunction "3_3") (pintype "passive"))
      (node (ref "U$7") (pin "IN_R") (pinfunction "IN_R_IN_R") (pintype "bidirectional"))
    )
    (net (code "27") (name "Net-(LED1-DO)") (class "Default")
      (node (ref "LED1") (pin "2-DOUT") (pinfunction "DO_2-DOUT") (pintype "output"))
      (node (ref "LED2") (pin "4-DIN") (pinfunction "DI_4-DIN") (pintype "input"))
    )
    (net (code "28") (name "Net-(LED2-DO)") (class "Default")
      (node (ref "LED2") (pin "2-DOUT") (pinfunction "DO_2-DOUT") (pintype "output"))
      (node (ref "LED3") (pin "4-DIN") (pinfunction "DI_4-DIN") (pintype "input"))
    )
    (net (code "29") (name "Net-(LED3-DO)") (class "Default")
      (node (ref "LED3") (pin "2-DOUT") (pinfunction "DO_2-DOUT") (pintype "output"))
      (node (ref "LED4") (pin "4-DIN") (pinfunction "DI_4-DIN") (pintype "input"))
    )
    (net (code "30") (name "Net-(LED4-DO)") (class "Default")
      (node (ref "LED4") (pin "2-DOUT") (pinfunction "DO_2-DOUT") (pintype "output"))
      (node (ref "LED5") (pin "4-DIN") (pinfunction "DI_4-DIN") (pintype "input"))
    )
    (net (code "31") (name "Net-(LED5-DO)") (class "Default")
      (node (ref "LED5") (pin "2-DOUT") (pinfunction "DO_2-DOUT") (pintype "output"))
      (node (ref "LED6") (pin "4-DIN") (pinfunction "DI_4-DIN") (pintype "input"))
    )
    (net (code "32") (name "Net-(LED6-DO)") (class "Default")
      (node (ref "LED6") (pin "2-DOUT") (pinfunction "DO_2-DOUT") (pintype "output"))
      (node (ref "LED7") (pin "4-DIN") (pinfunction "DI_4-DIN") (pintype "input"))
    )
    (net (code "33") (name "Net-(LED7-DO)") (class "Default")
      (node (ref "LED7") (pin "2-DOUT") (pinfunction "DO_2-DOUT") (pintype "output"))
      (node (ref "LED8") (pin "4-DIN") (pinfunction "DI_4-DIN") (pintype "input"))
    )
    (net (code "34") (name "Net-(LED8-DO)") (class "Default")
      (node (ref "LED8") (pin "2-DOUT") (pinfunction "DO_2-DOUT") (pintype "output"))
      (node (ref "LED9") (pin "4-DIN") (pinfunction "DI_4-DIN") (pintype "input"))
    )
    (net (code "35") (name "Net-(LED10-DI)") (class "Default")
      (node (ref "LED10") (pin "4-DIN") (pinfunction "DI_4-DIN") (pintype "input"))
      (node (ref "LED9") (pin "2-DOUT") (pinfunction "DO_2-DOUT") (pintype "output"))
    )
    (net (code "36") (name "Net-(LED10-DO)") (class "Default")
      (node (ref "LED10") (pin "2-DOUT") (pinfunction "DO_2-DOUT") (pintype "output"))
      (node (ref "LED11") (pin "4-DIN") (pinfunction "DI_4-DIN") (pintype "input"))
    )
    (net (code "37") (name "Net-(LED11-DO)") (class "Default")
      (node (ref "LED11") (pin "2-DOUT") (pinfunction "DO_2-DOUT") (pintype "output"))
      (node (ref "LED12") (pin "4-DIN") (pinfunction "DI_4-DIN") (pintype "input"))
    )
    (net (code "38") (name "Net-(LED12-DO)") (class "Default")
      (node (ref "LED12") (pin "2-DOUT") (pinfunction "DO_2-DOUT") (pintype "output"))
      (node (ref "LED13") (pin "4-DIN") (pinfunction "DI_4-DIN") (pintype "input"))
    )
    (net (code "39") (name "Net-(LED13-DO)") (class "Default")
      (node (ref "LED13") (pin "2-DOUT") (pinfunction "DO_2-DOUT") (pintype "output"))
      (node (ref "LED14") (pin "4-DIN") (pinfunction "DI_4-DIN") (pintype "input"))
    )
    (net (code "40") (name "Net-(LED14-DO)") (class "Default")
      (node (ref "LED14") (pin "2-DOUT") (pinfunction "DO_2-DOUT") (pintype "output"))
      (node (ref "LED15") (pin "4-DIN") (pinfunction "DI_4-DIN") (pintype "input"))
    )
    (net (code "41") (name "Net-(LED15-DO)") (class "Default")
      (node (ref "LED15") (pin "2-DOUT") (pinfunction "DO_2-DOUT") (pintype "output"))
      (node (ref "LED16") (pin "4-DIN") (pinfunction "DI_4-DIN") (pintype "input"))
    )
    (net (code "42") (name "Net-(LED17-DO)") (class "Default")
      (node (ref "LED17") (pin "2-DOUT") (pinfunction "DO_2-DOUT") (pintype "output"))
      (node (ref "LED18") (pin "4-DIN") (pinfunction "DI_4-DIN") (pintype "input"))
    )
    (net (code "43") (name "Net-(LED18-DO)") (class "Default")
      (node (ref "LED18") (pin "2-DOUT") (pinfunction "DO_2-DOUT") (pintype "output"))
      (node (ref "LED19") (pin "4-DIN") (pinfunction "DI_4-DIN") (pintype "input"))
    )
    (net (code "44") (name "Net-(LED19-DO)") (class "Default")
      (node (ref "LED19") (pin "2-DOUT") (pinfunction "DO_2-DOUT") (pintype "output"))
      (node (ref "LED20") (pin "4-DIN") (pinfunction "DI_4-DIN") (pintype "input"))
    )
    (net (code "45") (name "Net-(MEMS_FRONT_EX-SD)") (class "Default")
      (node (ref "MEMS_FRONT_EX") (pin "7") (pinfunction "SD_7") (pintype "output"))
      (node (ref "MEMS_FRONT_STD") (pin "6") (pinfunction "DATA_OUT_6") (pintype "output"))
      (node (ref "R14") (pin "1") (pinfunction "1_1") (pintype "passive"))
    )
    (net (code "46") (name "Net-(U$5-PadP$10)") (class "Default")
      (node (ref "U$5") (pin "P$10") (pinfunction "P$10_P$10") (pintype "bidirectional"))
      (node (ref "U$5") (pin "P$11") (pinfunction "P$11_P$11") (pintype "bidirectional"))
      (node (ref "U$5") (pin "P$12") (pinfunction "P$12_P$12") (pintype "bidirectional"))
      (node (ref "U$5") (pin "P$4") (pinfunction "P$4_P$4") (pintype "bidirectional"))
      (node (ref "U$5") (pin "P$5") (pinfunction "P$5_P$5") (pintype "bidirectional"))
      (node (ref "U$5") (pin "P$6") (pinfunction "P$6_P$6") (pintype "bidirectional"))
    )
    (net (code "47") (name "Net-(U$7-IN_GND)") (class "Default")
      (node (ref "AUDIO_IN") (pin "1") (pinfunction "1_1") (pintype "passive"))
      (node (ref "U$7") (pin "IN_G") (pinfunction "IN_GND_IN_G") (pintype "bidirectional"))
    )
    (net (code "48") (name "Net-(U$7-OUT_L+)") (class "Default")
      (node (ref "FOUT") (pin "1") (pinfunction "1_1") (pintype "passive"))
      (node (ref "FRONT_OUT") (pin "1") (pinfunction "1_1") (pintype "passive"))
      (node (ref "F_OUT") (pin "1") (pinfunction "1_1") (pintype "passive"))
      (node (ref "U$7") (pin "LOUT_H") (pinfunction "OUT_L+_LOUT_H") (pintype "bidirectional"))
    )
    (net (code "49") (name "Net-(U$7-OUT_L-)") (class "Default")
      (node (ref "FOUT") (pin "2") (pinfunction "2_2") (pintype "passive"))
      (node (ref "FRONT_OUT") (pin "2") (pinfunction "2_2") (pintype "passive"))
      (node (ref "F_OUT") (pin "2") (pinfunction "2_2") (pintype "passive"))
      (node (ref "U$7") (pin "LOUT_G") (pinfunction "OUT_L-_LOUT_G") (pintype "bidirectional"))
    )
    (net (code "50") (name "Net-(U$7-OUT_R+)") (class "Default")
      (node (ref "REAR_OUT") (pin "1") (pinfunction "1_1") (pintype "passive"))
      (node (ref "ROUT") (pin "1") (pinfunction "1_1") (pintype "passive"))
      (node (ref "R_OUT") (pin "1") (pinfunction "1_1") (pintype "passive"))
      (node (ref "U$7") (pin "ROUT_H") (pinfunction "OUT_R+_ROUT_H") (pintype "bidirectional"))
    )
    (net (code "51") (name "Net-(U$7-OUT_R-)") (class "Default")
      (node (ref "REAR_OUT") (pin "2") (pinfunction "2_2") (pintype "passive"))
      (node (ref "ROUT") (pin "2") (pinfunction "2_2") (pintype "passive"))
      (node (ref "R_OUT") (pin "2") (pinfunction "2_2") (pintype "passive"))
      (node (ref "U$7") (pin "ROUT_G") (pinfunction "OUT_R-_ROUT_G") (pintype "bidirectional"))
    )
    (net (code "52") (name "Net-(U3-VIN)") (class "Default")
      (node (ref "R10") (pin "2") (pinfunction "2_2") (pintype "passive"))
      (node (ref "U3") (pin "1") (pinfunction "VIN_1") (pintype "input"))
    )
    (net (code "53") (name "Net-(VMEL_FRONT-VDD)") (class "Default")
      (node (ref "C10") (pin "1") (pinfunction "1_1") (pintype "passive"))
      (node (ref "C8") (pin "1") (pinfunction "1_1") (pintype "passive"))
      (node (ref "R1") (pin "1") (pinfunction "1_1") (pintype "passive"))
      (node (ref "VMEL_FRONT") (pin "6") (pinfunction "VDD_6") (pintype "power_in"))
    )
    (net (code "54") (name "Net-(VMEL_REAR-ADDR)") (class "Default")
      (node (ref "C42") (pin "1") (pinfunction "1_1") (pintype "passive"))
      (node (ref "C43") (pin "1") (pinfunction "1_1") (pintype "passive"))
      (node (ref "R2") (pin "1") (pinfunction "1_1") (pintype "passive"))
      (node (ref "VMEL_REAR") (pin "4") (pinfunction "ADDR_4") (pintype "bidirectional"))
      (node (ref "VMEL_REAR") (pin "6") (pinfunction "VDD_6") (pintype "power_in"))
    )
    (net (code "55") (name "ONT") (class "Default")
      (node (ref "C37") (pin "1") (pinfunction "1_1") (pintype "passive"))
      (node (ref "U3") (pin "3") (pinfunction "ONT_3") (pintype "input"))
    )
    (net (code "56") (name "PDT") (class "Default")
      (node (ref "C2") (pin "1") (pinfunction "1_1") (pintype "passive"))
      (node (ref "U3") (pin "7") (pinfunction "PDT_7") (pintype "input"))
    )
    (net (code "57") (name "POT1") (class "Default")
      (node (ref "POT1") (pin "2") (pinfunction "2_2") (pintype "passive"))
      (node (ref "U$3") (pin "17/A3") (pinfunction "17/A3/T_17/A3") (pintype "bidirectional"))
      (node (ref "U$4") (pin "P$1") (pinfunction "P$1_P$1") (pintype "bidirectional"))
    )
    (net (code "58") (name "POT2") (class "Default")
      (node (ref "POT2") (pin "2") (pinfunction "2_2") (pintype "passive"))
      (node (ref "U$3") (pin "21/A7") (pinfunction "21/A7/PWM_21/A7") (pintype "bidirectional"))
      (node (ref "U$6") (pin "P$1") (pinfunction "P$1_P$1") (pintype "bidirectional"))
    )
    (net (code "59") (name "PWR_INT") (class "Default")
      (node (ref "R8") (pin "1") (pinfunction "1_1") (pintype "passive"))
      (node (ref "U$3") (pin "15/A1") (pinfunction "15/A1/T_15/A1") (pintype "bidirectional"))
      (node (ref "U3") (pin "5") (pinfunction "*INT_5") (pintype "output"))
    )
    (net (code "60") (name "PWR_KILL") (class "Default")
      (node (ref "U$3") (pin "8") (pinfunction "8/TX3_8") (pintype "bidirectional"))
      (node (ref "U3") (pin "8") (pinfunction "*KILL_8") (pintype "input"))
    )
    (net (code "61") (name "REAR_PRE_R") (class "Default")
      (node (ref "MEMS_REAR_EX") (pin "7") (pinfunction "SD_7") (pintype "output"))
      (node (ref "MEMS_REAR_STD") (pin "6") (pinfunction "DATA_OUT_6") (pintype "output"))
      (node (ref "R16") (pin "1") (pinfunction "1_1") (pintype "passive"))
    )
    (net (code "62") (name "SCL") (class "Default")
      (node (ref "R4") (pin "1") (pinfunction "1_1") (pintype "passive"))
      (node (ref "U$3") (pin "19/A5") (pinfunction "19/A5/T/SCL0_19/A5") (pintype "bidirectional"))
      (node (ref "U1") (pin "2") (pinfunction "SCL/SPC_2") (pintype "bidirectional"))
      (node (ref "U2") (pin "2") (pinfunction "SCL_2") (pintype "bidirectional"))
      (node (ref "VMEL_FRONT") (pin "5") (pinfunction "SCL_5") (pintype "input"))
      (node (ref "VMEL_REAR") (pin "5") (pinfunction "SCL_5") (pintype "input"))
    )
    (net (code "63") (name "SDA") (class "Default")
      (node (ref "R3") (pin "1") (pinfunction "1_1") (pintype "passive"))
      (node (ref "U$3") (pin "18/A4") (pinfunction "18/A4/T/SDA0_18/A4") (pintype "bidirectional"))
      (node (ref "U1") (pin "3") (pinfunction "SDA/SDI_3") (pintype "input"))
      (node (ref "U2") (pin "3") (pinfunction "SDA_3") (pintype "bidirectional"))
      (node (ref "VMEL_FRONT") (pin "2") (pinfunction "SDA_2") (pintype "bidirectional"))
      (node (ref "VMEL_REAR") (pin "2") (pinfunction "SDA_2") (pintype "bidirectional"))
    )
    (net (code "64") (name "SD_CS") (class "Default")
      (node (ref "J7") (pin "2") (pinfunction "CD/DAT3_2") (pintype "passive"))
      (node (ref "R11") (pin "1") (pinfunction "1_1") (pintype "passive"))
      (node (ref "U$3") (pin "10") (pinfunction "10/TX2/PWM_10") (pintype "bidirectional"))
    )
    (net (code "65") (name "SPI_CLK") (class "Default")
      (node (ref "J7") (pin "5") (pinfunction "CLK_5") (pintype "passive"))
      (node (ref "U$3") (pin "14/A0") (pinfunction "14/A1_14/A0") (pintype "bidirectional"))
    )
    (net (code "66") (name "VEML_INT_1") (class "Default")
      (node (ref "VMEL_FRONT") (pin "3") (pinfunction "INT_3") (pintype "output"))
    )
    (net (code "67") (name "VEML_INT_2") (class "Default")
      (node (ref "VMEL_REAR") (pin "3") (pinfunction "INT_3") (pintype "output"))
    )
    (net (code "68") (name "_BCLK") (class "Default")
      (node (ref "R5") (pin "2") (pinfunction "2_2") (pintype "passive"))
      (node (ref "U$3") (pin "9") (pinfunction "9/RX2/PWM_9") (pintype "bidirectional"))
    )
    (net (code "69") (name "_LRCLK") (class "Default")
      (node (ref "R7") (pin "2") (pinfunction "2_2") (pintype "passive"))
      (node (ref "U$3") (pin "23/A9") (pinfunction "23/A9/T/PWM_23/A9") (pintype "bidirectional"))
    )
    (net (code "70") (name "unconnected-(J7-CD_SW-Pad9)") (class "Default")
      (node (ref "J7") (pin "9") (pinfunction "CD_SW_9") (pintype "passive"))
    )
    (net (code "71") (name "unconnected-(J7-DAT1-Pad8)") (class "Default")
      (node (ref "J7") (pin "8") (pinfunction "DAT1_8") (pintype "passive"))
    )
    (net (code "72") (name "unconnected-(J7-DAT2-Pad1)") (class "Default")
      (node (ref "J7") (pin "1") (pinfunction "DAT2_1") (pintype "passive"))
    )
    (net (code "73") (name "unconnected-(LED20-DO-Pad2-DOUT)") (class "Default")
      (node (ref "LED20") (pin "2-DOUT") (pinfunction "DO_2-DOUT") (pintype "output"))
    )
    (net (code "74") (name "unconnected-(PWR-PadP$2)") (class "Default")
      (node (ref "PWR") (pin "P$2") (pinfunction "P$2_P$2") (pintype "bidirectional"))
    )
    (net (code "75") (name "unconnected-(U1-REGOUT-Pad14)") (class "Default")
      (node (ref "U1") (pin "14") (pinfunction "REGOUT_14") (pintype "passive"))
    )
    (net (code "76") (name "unconnected-(U1-RESV7-Pad7)") (class "Default")
      (node (ref "U1") (pin "7") (pinfunction "RESV7_7") (pintype "passive"))
    )
  )
)
